# Pass_Transistor.net
KiCad netlist of a schematic drawn in Altium Designer
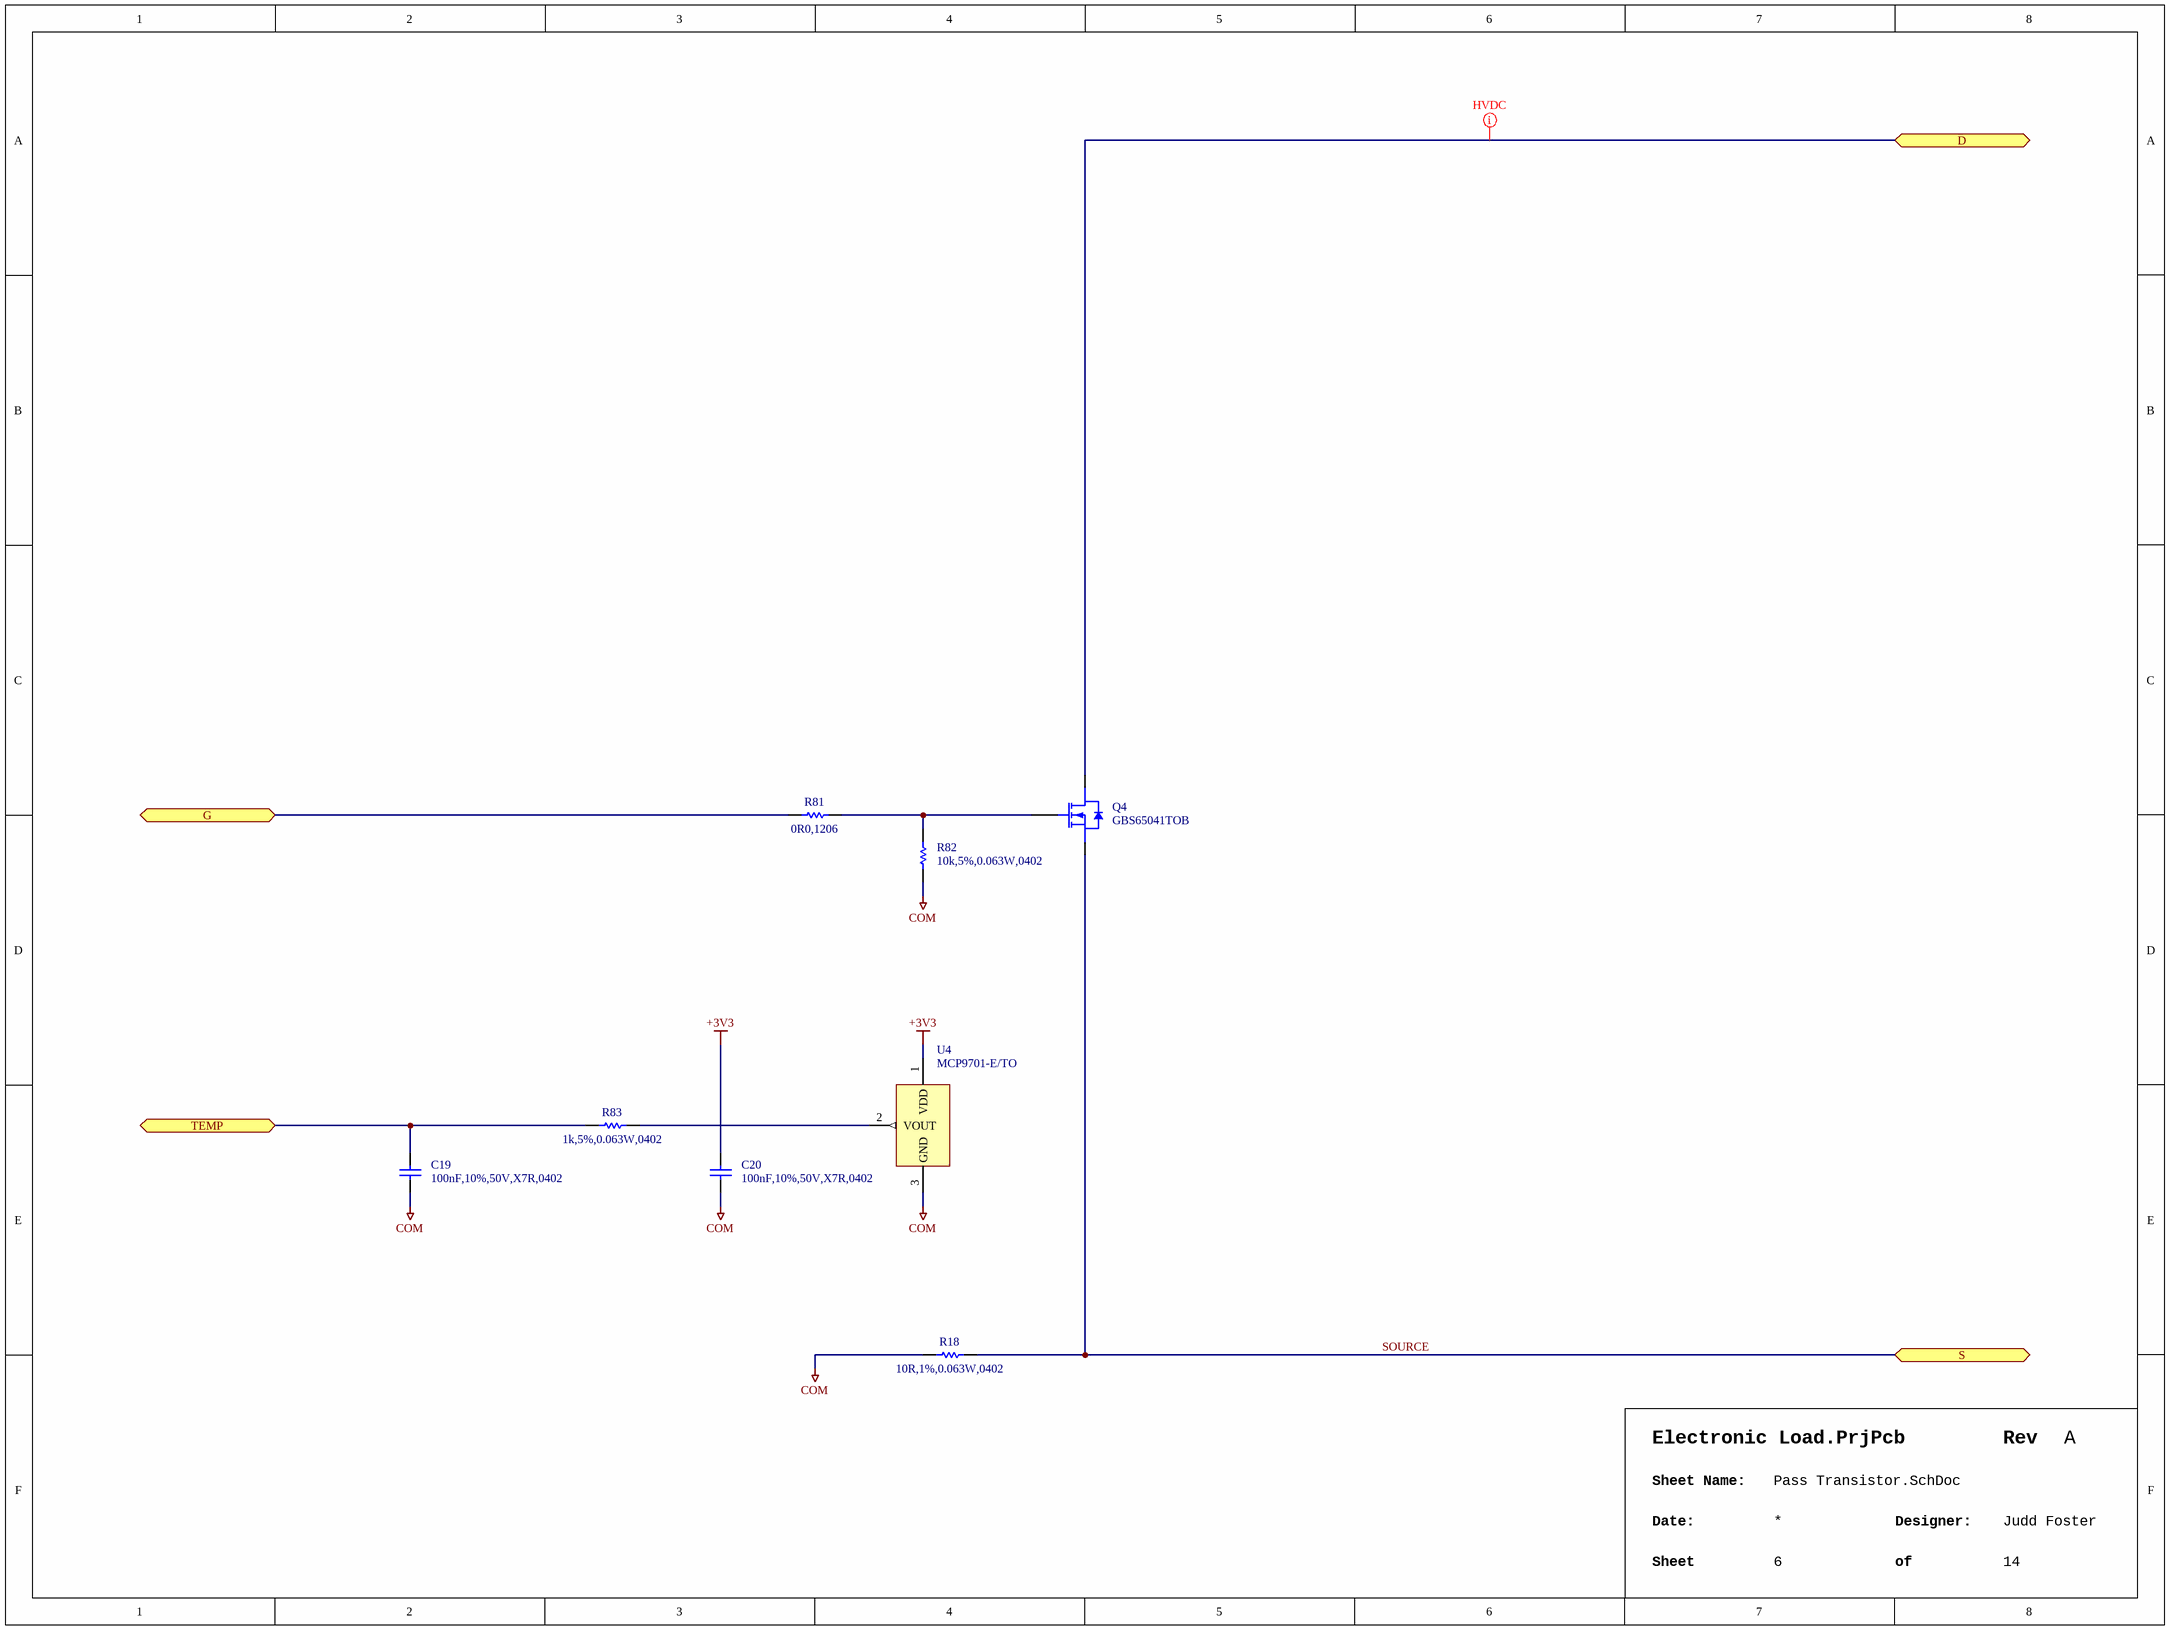
[diagram p0: Pass Transistor.SchDoc]

(export (version "E")
  (design (tool "Eeschema 10.0.6"))
  (components
    (comp (ref "C19")
      (value "100nF,10%,50V,X7R,0402")
      (footprint "CAPC1005X06N")
      (description "50V 100nF X7R Â±10% 0402 Ceramic Capacitors ROHS")
      (fields
        (field (name "MANUFACTURER 1 PART NUMBER") "GRM155R71H104KE14D")
        (field (name "VENDOR 1 PART NUMBER") "C77020")
        (field (name "CREATEDBY") "Judd Foster")
      )
      (libsource (lib "Component Library") (part "CAP,NPOL"))
    )
    (comp (ref "C20")
      (value "100nF,10%,50V,X7R,0402")
      (footprint "CAPC1005X06N")
      (description "50V 100nF X7R Â±10% 0402 Ceramic Capacitors ROHS")
      (fields
        (field (name "MANUFACTURER 1 PART NUMBER") "GRM155R71H104KE14D")
        (field (name "VENDOR 1 PART NUMBER") "C77020")
        (field (name "CREATEDBY") "Judd Foster")
      )
      (libsource (lib "Component Library") (part "CAP,NPOL"))
    )
    (comp (ref "Q4")
      (value "GBS65041TOB")
      (footprint "GOSEMICON_PKG_TO-247")
      (description "650V 66A 313W 34mÎ©@10V 4V@1mA 1 N-Channel TO-247 Single FETs, MOSFETs ROHS")
      (fields (field (name "VENDOR 1 PART NUMBER") "C5451736") (field (name "CREATEDBY") "Judd Foster"))
      (libsource (lib "Component Library") (part "MOSFET,N Ch,650V,66A"))
    )
    (comp (ref "R18")
      (value "10R,1%,0.063W,0402")
      (footprint "RESC1005X04N")
      (description "10 Ohms ï¿½1% 0.063W, 1/16W Chip Resistor 0402 (1005 Metric) Automotive AEC-Q200 Thick Film")
      (fields
        (field (name "MANUFACTURER 1 PART NUMBER") "ERJ-2RKF10R0X")
        (field (name "VENDOR 1 PART NUMBER") "P10.0LCT-ND")
        (field (name "CREATEDBY") "Judd Foster")
      )
      (libsource (lib "Component Library") (part "RES,10R,1%,0.063W,0402"))
    )
    (comp (ref "R81")
      (value "0R0,1206")
      (footprint "RESC3216X06N")
      (description "0 Ohms Jumper Chip Resistor 1206 (3216 Metric) Automotive AEC-Q200 Thick Film")
      (fields
        (field (name "MANUFACTURER 1 PART NUMBER") "RMCF1206ZT0R00")
        (field (name "VENDOR 1 PART NUMBER") "RMCF1206ZT0R00CT-ND")
        (field (name "CREATEDBY") "Judd Foster")
      )
      (libsource (lib "Component Library") (part "RES,0R0,1206"))
    )
    (comp (ref "R82")
      (value "10k,5%,0.063W,0402")
      (footprint "RESC1005X04N")
      (description "10 kOhms ï¿½5% 0.063W, 1/16W Chip Resistor 0402 (1005 Metric) Automotive AEC-Q200 Thick Film")
      (fields
        (field (name "MANUFACTURER 1 PART NUMBER") "RMCF0402JT10K0")
        (field (name "VENDOR 1 PART NUMBER") "RMCF0402JT10K0CT-ND")
        (field (name "CREATEDBY") "Judd Foster")
      )
      (libsource (lib "Component Library") (part "RES,10k,5%,0.063W,0402"))
    )
    (comp (ref "R83")
      (value "1k,5%,0.063W,0402")
      (footprint "RESC1005X04N")
      (description "1 kOhms ï¿½5% 0.063W, 1/16W Chip Resistor 0402 (1005 Metric) Automotive AEC-Q200 Thick Film")
      (fields
        (field (name "MANUFACTURER 1 PART NUMBER") "RMCF0402JT1K00")
        (field (name "VENDOR 1 PART NUMBER") "RMCF0402JT1K00CT-ND")
        (field (name "CREATEDBY") "Judd Foster")
      )
      (libsource (lib "Component Library") (part "RES,1k,5%,0.063W,0402"))
    )
    (comp (ref "U4")
      (value "MCP9701-E/TO")
      (footprint "TO-92")
      (description "Temperature Sensor Analog, Local -10ï¿½C ~ 125ï¿½C 19.5mV/ï¿½C TO-92-3")
      (fields
        (field (name "VENDOR 1 PART NUMBER") "MCP9701-E/TO-ND")
        (field (name "CREATEDBY") "Judd Foster")
      )
      (libsource (lib "Component Library") (part "MCP9701-E/TO"))
    )
  )
  (nets
    (net (code "1") (name "+3V3") (class "Default")
      (node (ref "C20") (pin "2") (pinfunction "2_2") (pintype "passive"))
      (node (ref "U4") (pin "1") (pinfunction "VDD_1") (pintype "power_in"))
    )
    (net (code "2") (name "/D") (class "Default")
      (node (ref "Q4") (pin "2") (pinfunction "D_2") (pintype "passive"))
    )
    (net (code "3") (name "/G") (class "Default")
      (node (ref "R81") (pin "1") (pinfunction "1_1") (pintype "passive"))
    )
    (net (code "4") (name "/SOURCE") (class "Default")
      (node (ref "Q4") (pin "3") (pinfunction "S_3") (pintype "passive"))
      (node (ref "R18") (pin "2") (pinfunction "2_2") (pintype "passive"))
    )
    (net (code "5") (name "/TEMP") (class "Default")
      (node (ref "C19") (pin "2") (pinfunction "2_2") (pintype "passive"))
      (node (ref "R83") (pin "1") (pinfunction "1_1") (pintype "passive"))
    )
    (net (code "6") (name "COM") (class "Default")
      (node (ref "C19") (pin "1") (pinfunction "1_1") (pintype "passive"))
      (node (ref "C20") (pin "1") (pinfunction "1_1") (pintype "passive"))
      (node (ref "R18") (pin "1") (pinfunction "1_1") (pintype "passive"))
      (node (ref "R82") (pin "1") (pinfunction "1_1") (pintype "passive"))
      (node (ref "U4") (pin "3") (pinfunction "GND_3") (pintype "power_in"))
    )
    (net (code "7") (name "Net-(Q4-G)") (class "Default")
      (node (ref "Q4") (pin "1") (pinfunction "G_1") (pintype "passive"))
      (node (ref "R81") (pin "2") (pinfunction "2_2") (pintype "passive"))
      (node (ref "R82") (pin "2") (pinfunction "2_2") (pintype "passive"))
    )
    (net (code "8") (name "Net-(U4-VOUT)") (class "Default")
      (node (ref "R83") (pin "2") (pinfunction "2_2") (pintype "passive"))
      (node (ref "U4") (pin "2") (pinfunction "VOUT_2") (pintype "output"))
    )
  )
)
